# bq25611d_Battery_Charger.net
KiCad netlist of a schematic drawn in Altium Designer
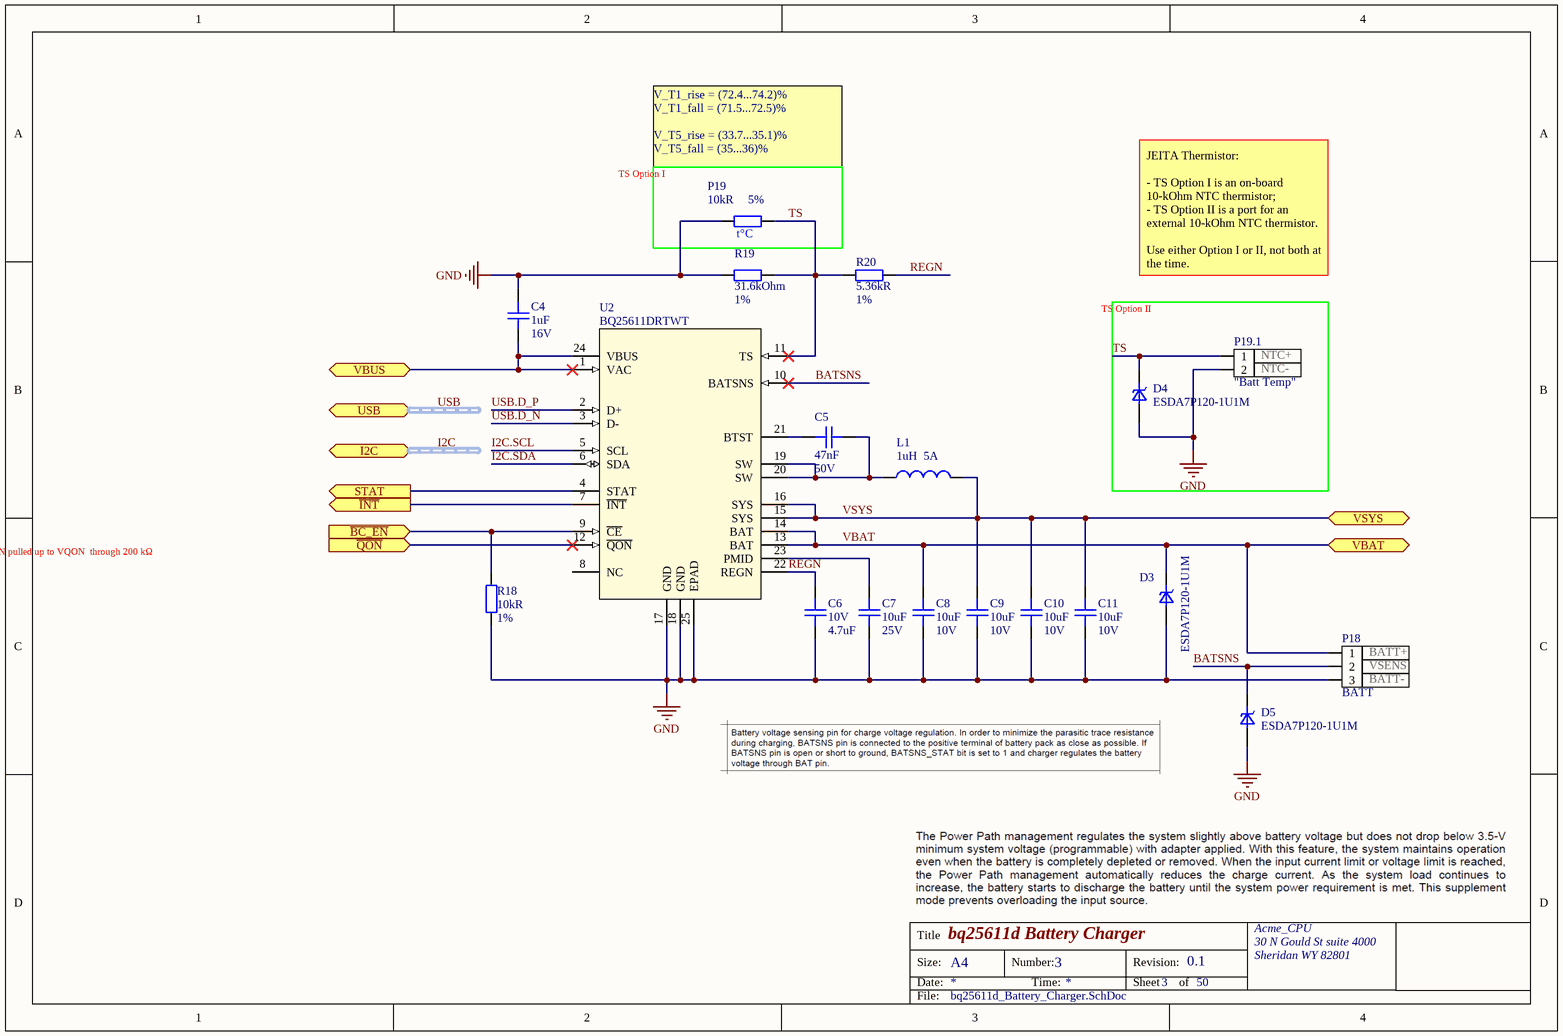
[diagram p0: bq25611d_Battery_Charger.SchDoc]

(export (version "E")
  (design (tool "Eeschema 10.0.6"))
  (components
    (comp (ref "C4")
      (value "CAP CER 1UF 16V X5R 0603")
      (footprint "C0603")
      (description "1µF ±10% 16V Ceramic Capacitor X5R 0603 (1608 Metric)")
      (fields
        (field (name "MANUFACTURER") "Yageo")
        (field (name "MANUFACTURER PART NUMBER") "CC0603KRX5R7BB105")
        (field (name "CAPACITANCE") "1uF")
        (field (name "VOLTAGE RATING") "16V")
      )
      (libsource (lib "capacitors_smd") (part "CAP CER 1UF 16V X5R 0603"))
    )
    (comp (ref "C5")
      (value "CAP CER 0.047UF 50V X7R 0402")
      (footprint "C0402")
      (description "0.047µF ±10% 50V Ceramic Capacitor X7R 0402 (1005 Metric)")
      (fields
        (field (name "MANUFACTURER") "TDK")
        (field (name "MANUFACTURER PART NUMBER") "CGA2B3X7R1H473K050BB")
        (field (name "CAPACITANCE") "47nF")
        (field (name "VOLTAGE RATING") "50V")
      )
      (libsource (lib "capacitors_smd") (part "CAP CER 0.047UF 50V X7R 0402"))
    )
    (comp (ref "C6")
      (value "CAP CER 4.7UF 10V X5R 0603")
      (footprint "C0603")
      (description "4.7µF ±10% 10V Ceramic Capacitor X5R 0603 (1608 Metric)")
      (fields
        (field (name "MANUFACTURER") "Yageo")
        (field (name "MANUFACTURER PART NUMBER") "CC0603KRX5R6BB475")
        (field (name "VOLTAGE RATING") "10V")
        (field (name "CAPACITANCE") "4.7uF")
      )
      (libsource (lib "capacitors_smd") (part "CAP CER 4.7UF 10V X5R 0603"))
    )
    (comp (ref "C7")
      (value "CAP CER 10UF 25V X7R 1206")
      (footprint "C1206")
      (description "10µF ±10% 25V Ceramic Capacitor X7R 1206 (3216 Metric)")
      (fields
        (field (name "MANUFACTURER") "Yageo")
        (field (name "MANUFACTURER PART NUMBER") "CC1206KKX7R8BB106")
        (field (name "CAPACITANCE") "10uF")
        (field (name "VOLTAGE RATING") "25V")
      )
      (libsource (lib "capacitors_smd") (part "CAP CER 10UF 25V X7R 1206"))
    )
    (comp (ref "C8")
      (value "CAP CER 10uF X7R 10% 0805")
      (footprint "C0805")
      (description "Capacitor,10uF,10V,X7R,10%,0805,Murata")
      (fields
        (field (name "MANUFACTURER") "Murata")
        (field (name "MANUFACTURER PART NUMBER") "GRM21BR71A106KA73L")
        (field (name "CAPACITANCE") "10uF")
        (field (name "VOLTAGE RATING") "10V")
      )
      (libsource (lib "capacitors_smd") (part "CAP CER 10uF X7R 10% 0805"))
    )
    (comp (ref "C9")
      (value "CAP CER 10uF X7R 10% 0805")
      (footprint "C0805")
      (description "Capacitor,10uF,10V,X7R,10%,0805,Murata")
      (fields
        (field (name "MANUFACTURER") "Murata")
        (field (name "MANUFACTURER PART NUMBER") "GRM21BR71A106KA73L")
        (field (name "CAPACITANCE") "10uF")
        (field (name "VOLTAGE RATING") "10V")
      )
      (libsource (lib "capacitors_smd") (part "CAP CER 10uF X7R 10% 0805"))
    )
    (comp (ref "C10")
      (value "CAP CER 10uF X7R 10% 0805")
      (footprint "C0805")
      (description "Capacitor,10uF,10V,X7R,10%,0805,Murata")
      (fields
        (field (name "MANUFACTURER") "Murata")
        (field (name "MANUFACTURER PART NUMBER") "GRM21BR71A106KA73L")
        (field (name "CAPACITANCE") "10uF")
        (field (name "VOLTAGE RATING") "10V")
      )
      (libsource (lib "capacitors_smd") (part "CAP CER 10uF X7R 10% 0805"))
    )
    (comp (ref "C11")
      (value "CAP CER 10uF X7R 10% 0805")
      (footprint "C0805")
      (description "Capacitor,10uF,10V,X7R,10%,0805,Murata")
      (fields
        (field (name "MANUFACTURER") "Murata")
        (field (name "MANUFACTURER PART NUMBER") "GRM21BR71A106KA73L")
        (field (name "CAPACITANCE") "10uF")
        (field (name "VOLTAGE RATING") "10V")
      )
      (libsource (lib "capacitors_smd") (part "CAP CER 10uF X7R 10% 0805"))
    )
    (comp (ref "D3")
      (value "ESDA7P120-1U1M")
      (footprint "ST_QFN_1610")
      (description "11.5V Clamp 120A (8/20µs) Ipp Tvs Diode Surface Mount 1610")
      (fields (field (name "MANUFACTURER") "STMicroelectronics"))
      (libsource (lib "diodes_tvs") (part "TVS DIODE ESDA7P120-1U1M 5.5V 11.5V 1610"))
    )
    (comp (ref "D4")
      (value "ESDA7P120-1U1M")
      (footprint "ST_QFN_1610")
      (description "11.5V Clamp 120A (8/20µs) Ipp Tvs Diode Surface Mount 1610")
      (fields (field (name "MANUFACTURER") "STMicroelectronics"))
      (libsource (lib "diodes_tvs") (part "TVS DIODE ESDA7P120-1U1M 5.5V 11.5V 1610"))
    )
    (comp (ref "D5")
      (value "ESDA7P120-1U1M")
      (footprint "ST_QFN_1610")
      (description "11.5V Clamp 120A (8/20µs) Ipp Tvs Diode Surface Mount 1610")
      (fields (field (name "MANUFACTURER") "STMicroelectronics"))
      (libsource (lib "diodes_tvs") (part "TVS DIODE ESDA7P120-1U1M 5.5V 11.5V 1610"))
    )
    (comp (ref "L1")
      (value "FIXED IND 1UH 5A 24 MOHM SMD")
      (footprint "IND_IHLP-1212B00")
      (description "1µH Shielded Molded Inductor 5A 24mOhm Max Nonstandard")
      (fields
        (field (name "MANUFACTURER") "Vishay Dale")
        (field (name "MANUFACTURER PART NUMBER") "IHLP1212BZER1R0M11")
        (field (name "INDUCTANCE") "1uH")
        (field (name "CURRENT RATING") "5A")
      )
      (libsource (lib "inductors_smd") (part "FIXED IND 1UH 5A 24 MOHM SMD"))
    )
    (comp (ref "P18")
      (value "BATT")
      (footprint "CONN_S3B-ZR_JST")
      (description "Connector Header Through Hole, Right Angle 3 position 0.059\" (1.50mm)")
      (fields
        (field (name "MANUFACTURER") "JST")
        (field (name "MANUFACTURER PART NUMBER") "S3B-ZR(LF)(SN)")
        (field (name "PIN_1") "BATT+")
        (field (name "PIN_2") "VSENS")
        (field (name "PIN_3") "BATT-")
      )
      (libsource (lib "connectors_header") (part "CONN HEADER TH R/A 3POS 1.5MM"))
    )
    (comp (ref "P19")
      (value "THERMISTOR NTC 10KOHM 3380K 0603")
      (footprint "R0603")
      (description "NTC Thermistor 10k 0603 (1608 Metric)")
      (fields
        (field (name "MANUFACTURER") "Panasonic")
        (field (name "MANUFACTURER PART NUMBER") "ERT-J1VG103JA")
        (field (name "RESISTANCE") "10kR")
        (field (name "TOLERANCE") "5%")
      )
      (libsource (lib "thermistors_smd") (part "THERMISTOR NTC 10KOHM 3380K 0603"))
    )
    (comp (ref "P19.1")
      (value "\"Batt Temp\"")
      (footprint "CONN_S2B-ZR_JST")
      (description "Connector Header Through Hole, Right Angle 2 position 0.059\" (1.50mm)")
      (fields
        (field (name "MANUFACTURER") "JST")
        (field (name "MANUFACTURER PART NUMBER") "S2B-ZR(LF)(SN)")
        (field (name "PIN_1") "NTC+")
        (field (name "PIN_2") "NTC-")
      )
      (libsource (lib "connectors_header") (part "CONN HEADER TH R/A 2POS 1.5MM"))
    )
    (comp (ref "R18")
      (value "RES SMD 10K OHM 1% 1/16W 0402")
      (footprint "R0402")
      (description "10 kOhms ±1% 0.063W, 1/16W Chip Resistor 0402 (1005 Metric) Moisture Resistant Thick Film")
      (fields
        (field (name "MANUFACTURER PART NUMBER") "RC0402FR-0710KP")
        (field (name "MANUFACTURER") "Yageo")
        (field (name "RESISTANCE") "10kR")
        (field (name "TOLERANCE") "1%")
      )
      (libsource (lib "resistors_smd") (part "RES SMD 10K OHM 1% 1/16W 0402"))
    )
    (comp (ref "R19")
      (value "RES SMD 31.6K OHM 1% 1/16W 0402")
      (footprint "R0402")
      (description "31.6 kOhms ±1% 0.063W, 1/16W Chip Resistor 0402 (1005 Metric) Moisture Resistant Thick Film")
      (fields
        (field (name "MANUFACTURER PART NUMBER") "RC0402FR-0731K6L")
        (field (name "MANUFACTURER") "Yageo")
        (field (name "RESISTANCE") "31.6kOhm")
        (field (name "TOLERANCE") "1%")
      )
      (libsource (lib "resistors_smd") (part "RES SMD 31.6K OHM 1% 1/16W 0402"))
    )
    (comp (ref "R20")
      (value "RES SMD 5.36K OHM 1% 1/16W 0402")
      (footprint "R0402")
      (description "5.36 kOhms ±1% 0.063W, 1/16W Chip Resistor 0402 (1005 Metric) Moisture Resistant Thick Film")
      (fields
        (field (name "MANUFACTURER PART NUMBER") "RC0402FR-075K36L")
        (field (name "MANUFACTURER") "Yageo")
        (field (name "RESISTANCE") "5.36kR")
        (field (name "TOLERANCE") "1%")
      )
      (libsource (lib "resistors_smd") (part "RES SMD 5.36K OHM 1% 1/16W 0402"))
    )
    (comp (ref "U2")
      (value "BQ25611DRTWT")
      (footprint "RTW0024")
      (description "Charger IC Lithium Ion/Polymer 24-WQFN (4x4)")
      (fields (field (name "MANUFACTURER") "Texas Instruments"))
      (libsource (lib "BLDC_Motor_Driver") (part "IC BQ25611DRTWR BATTERY CHARGER WQFN-24"))
    )
  )
  (nets
    (net (code "3") (name "/BATSNS") (class "Default")
      (node (ref "D5") (pin "1") (pinfunction "K_1") (pintype "passive"))
      (node (ref "P18") (pin "2") (pinfunction "2_2") (pintype "passive"))
      (node (ref "U2") (pin "10") (pinfunction "BATSNS_10") (pintype "input"))
    )
    (net (code "4") (name "/BC_EN") (class "Default")
      (node (ref "R18") (pin "1") (pinfunction "1_1") (pintype "passive"))
      (node (ref "U2") (pin "9") (pinfunction "CE_9") (pintype "input"))
    )
    (net (code "5") (name "/I2C.SCL") (class "Default")
      (node (ref "U2") (pin "5") (pinfunction "SCL_5") (pintype "input"))
    )
    (net (code "6") (name "/I2C.SDA") (class "Default")
      (node (ref "U2") (pin "6") (pinfunction "SDA_6") (pintype "bidirectional"))
    )
    (net (code "7") (name "/INT") (class "Default")
      (node (ref "U2") (pin "7") (pinfunction "INT_7") (pintype "open_collector"))
    )
    (net (code "8") (name "/QON") (class "Default")
      (node (ref "U2") (pin "12") (pinfunction "QON_12") (pintype "input+no_connect"))
    )
    (net (code "9") (name "/REGN") (class "Default")
      (node (ref "C6") (pin "2") (pinfunction "2_2") (pintype "passive"))
      (node (ref "R20") (pin "1") (pinfunction "1_1") (pintype "passive"))
      (node (ref "U2") (pin "22") (pinfunction "REGN_22") (pintype "power_in"))
    )
    (net (code "10") (name "/STAT") (class "Default")
      (node (ref "U2") (pin "4") (pinfunction "STAT_4") (pintype "open_collector"))
    )
    (net (code "11") (name "/TS") (class "Default")
      (node (ref "D4") (pin "1") (pinfunction "K_1") (pintype "passive"))
      (node (ref "P19") (pin "1") (pinfunction "1_1") (pintype "passive"))
      (node (ref "P19.1") (pin "1") (pinfunction "1_1") (pintype "passive"))
      (node (ref "R19") (pin "2") (pinfunction "2_2") (pintype "passive"))
      (node (ref "R20") (pin "2") (pinfunction "2_2") (pintype "passive"))
      (node (ref "U2") (pin "11") (pinfunction "TS_11") (pintype "input"))
    )
    (net (code "12") (name "/USB.D_N") (class "Default")
      (node (ref "U2") (pin "3") (pinfunction "D-_3") (pintype "input"))
    )
    (net (code "13") (name "/USB.D_P") (class "Default")
      (node (ref "U2") (pin "2") (pinfunction "D+_2") (pintype "input"))
    )
    (net (code "14") (name "/VBAT") (class "Default")
      (node (ref "C8") (pin "2") (pinfunction "2_2") (pintype "passive"))
      (node (ref "D3") (pin "1") (pinfunction "K_1") (pintype "passive"))
      (node (ref "P18") (pin "1") (pinfunction "1_1") (pintype "passive"))
      (node (ref "U2") (pin "13") (pinfunction "BAT_13") (pintype "power_in"))
      (node (ref "U2") (pin "14") (pinfunction "BAT_14") (pintype "power_in"))
    )
    (net (code "15") (name "/VBUS") (class "Default")
      (node (ref "C4") (pin "2") (pinfunction "2_2") (pintype "passive"))
      (node (ref "U2") (pin "1") (pinfunction "VAC_1") (pintype "input"))
      (node (ref "U2") (pin "24") (pinfunction "VBUS_24") (pintype "power_in"))
    )
    (net (code "16") (name "/VSYS") (class "Default")
      (node (ref "C10") (pin "2") (pinfunction "2_2") (pintype "passive"))
      (node (ref "C11") (pin "2") (pinfunction "2_2") (pintype "passive"))
      (node (ref "C9") (pin "2") (pinfunction "2_2") (pintype "passive"))
      (node (ref "L1") (pin "2") (pinfunction "2_2") (pintype "passive"))
      (node (ref "U2") (pin "15") (pinfunction "SYS_15") (pintype "power_in"))
      (node (ref "U2") (pin "16") (pinfunction "SYS_16") (pintype "power_in"))
    )
    (net (code "19") (name "GND") (class "Default")
      (node (ref "C10") (pin "1") (pinfunction "1_1") (pintype "passive"))
      (node (ref "C11") (pin "1") (pinfunction "1_1") (pintype "passive"))
      (node (ref "C4") (pin "1") (pinfunction "1_1") (pintype "passive"))
      (node (ref "C6") (pin "1") (pinfunction "1_1") (pintype "passive"))
      (node (ref "C7") (pin "1") (pinfunction "1_1") (pintype "passive"))
      (node (ref "C8") (pin "1") (pinfunction "1_1") (pintype "passive"))
      (node (ref "C9") (pin "1") (pinfunction "1_1") (pintype "passive"))
      (node (ref "D3") (pin "2") (pinfunction "A_2") (pintype "passive"))
      (node (ref "D4") (pin "2") (pinfunction "A_2") (pintype "passive"))
      (node (ref "D5") (pin "2") (pinfunction "A_2") (pintype "passive"))
      (node (ref "P18") (pin "3") (pinfunction "3_3") (pintype "passive"))
      (node (ref "P19") (pin "2") (pinfunction "2_2") (pintype "passive"))
      (node (ref "P19.1") (pin "2") (pinfunction "2_2") (pintype "passive"))
      (node (ref "R18") (pin "2") (pinfunction "2_2") (pintype "passive"))
      (node (ref "R19") (pin "1") (pinfunction "1_1") (pintype "passive"))
      (node (ref "U2") (pin "17") (pinfunction "GND_17") (pintype "power_in"))
      (node (ref "U2") (pin "18") (pinfunction "GND_18") (pintype "power_in"))
      (node (ref "U2") (pin "25") (pinfunction "EPAD_25") (pintype "power_in"))
    )
    (net (code "20") (name "Net-(C5-Pad2)") (class "Default")
      (node (ref "C5") (pin "2") (pinfunction "2_2") (pintype "passive"))
      (node (ref "L1") (pin "1") (pinfunction "1_1") (pintype "passive"))
      (node (ref "U2") (pin "19") (pinfunction "SW_19") (pintype "power_in"))
      (node (ref "U2") (pin "20") (pinfunction "SW_20") (pintype "power_in"))
    )
    (net (code "21") (name "Net-(U2-BTST)") (class "Default")
      (node (ref "C5") (pin "1") (pinfunction "1_1") (pintype "passive"))
      (node (ref "U2") (pin "21") (pinfunction "BTST_21") (pintype "power_in"))
    )
    (net (code "22") (name "Net-(U2-PMID)") (class "Default")
      (node (ref "C7") (pin "2") (pinfunction "2_2") (pintype "passive"))
      (node (ref "U2") (pin "23") (pinfunction "PMID_23") (pintype "power_in"))
    )
    (net (code "23") (name "unconnected-(U2-NC-Pad8)") (class "Default")
      (node (ref "U2") (pin "8") (pinfunction "NC_8") (pintype "passive"))
    )
  )
)
